# 32u4_Simple_Breakout.net
KiCad netlist of a schematic drawn in EAGLE
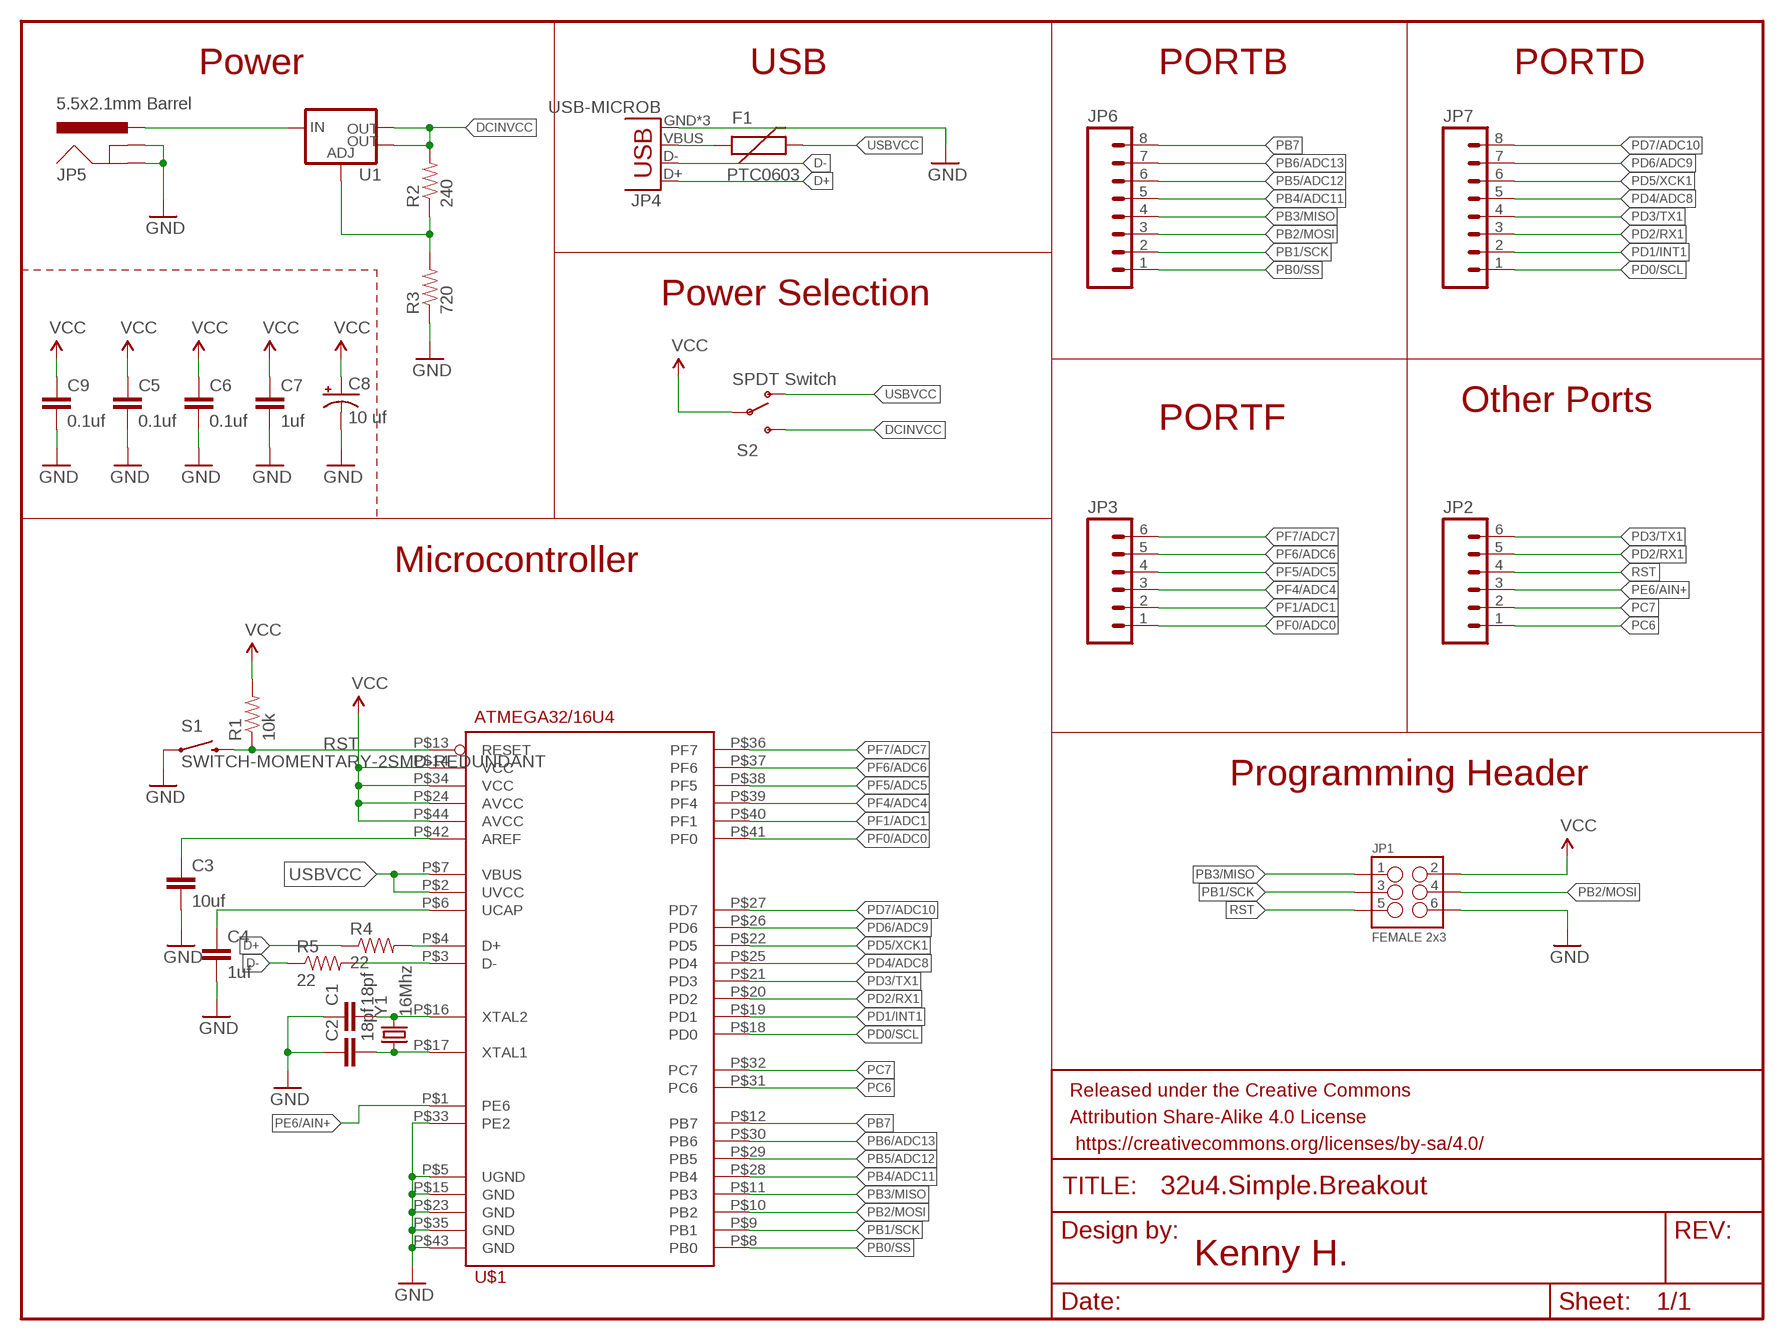
[diagram p0: schematic, sheet 1]

(export (version "E")
  (design (tool "Eeschema 10.0.6"))
  (components
    (comp (ref "C1")
      (value "18pf")
      (footprint "eagle-import:0603-CAP")
      (libsource (lib "eagle-import") (part "CAP0603-CAP"))
    )
    (comp (ref "C2")
      (value "18pf")
      (footprint "eagle-import:0603-CAP")
      (libsource (lib "eagle-import") (part "CAP0603-CAP"))
    )
    (comp (ref "C3")
      (value "10uf")
      (footprint "eagle-import:0603-CAP")
      (libsource (lib "eagle-import") (part "CAP0603-CAP"))
    )
    (comp (ref "C4")
      (value "1uf")
      (footprint "eagle-import:0603-CAP")
      (libsource (lib "eagle-import") (part "CAP0603-CAP"))
    )
    (comp (ref "C5")
      (value "0.1uf")
      (footprint "eagle-import:0603-CAP")
      (libsource (lib "eagle-import") (part "CAP0603-CAP"))
    )
    (comp (ref "C6")
      (value "0.1uf")
      (footprint "eagle-import:0603-CAP")
      (libsource (lib "eagle-import") (part "CAP0603-CAP"))
    )
    (comp (ref "C7")
      (value "1uf")
      (footprint "eagle-import:0603-CAP")
      (libsource (lib "eagle-import") (part "CAP0603-CAP"))
    )
    (comp (ref "C8")
      (value "10 uf")
      (footprint "eagle-import:CPOL-RADIAL-10UF-25V")
      (libsource (lib "eagle-import") (part "CAP_POLPTH2"))
    )
    (comp (ref "C9")
      (value "0.1uf")
      (footprint "eagle-import:0603-CAP")
      (libsource (lib "eagle-import") (part "CAP0603-CAP"))
    )
    (comp (ref "F1")
      (value "PTC0603")
      (footprint "eagle-import:0603")
      (libsource (lib "eagle-import") (part "PTC0603"))
    )
    (comp (ref "FRAME1")
      (value "FRAME-LETTER")
      (footprint "eagle-import:CREATIVE_COMMONS")
      (libsource (lib "eagle-import") (part "FRAME-LETTER"))
    )
    (comp (ref "JP1")
      (value "FEMALE 2x3")
      (footprint "eagle-import:2X3")
      (libsource (lib "eagle-import") (part "M03X2FEMALE"))
    )
    (comp (ref "JP2")
      (value "M06FEMALE_LOCK")
      (footprint "eagle-import:1X06_FEMALE_LOCK.010")
      (libsource (lib "eagle-import") (part "M06FEMALE_LOCK"))
    )
    (comp (ref "JP3")
      (value "M06FEMALE_LOCK")
      (footprint "eagle-import:1X06_FEMALE_LOCK.010")
      (libsource (lib "eagle-import") (part "M06FEMALE_LOCK"))
    )
    (comp (ref "JP4")
      (value "USB-MICROB")
      (footprint "eagle-import:USB-MICROB")
      (libsource (lib "eagle-import") (part "USB-MICROB"))
    )
    (comp (ref "JP5")
      (value "5.5x2.1mm Barrel")
      (footprint "eagle-import:POWER_JACK_SMD")
      (libsource (lib "eagle-import") (part "POWER_JACKSMD"))
    )
    (comp (ref "JP6")
      (value "M08FEMALE_LOCK")
      (footprint "eagle-import:1X08_FEMALE_LOCK")
      (libsource (lib "eagle-import") (part "M08FEMALE_LOCK"))
    )
    (comp (ref "JP7")
      (value "M08FEMALE_LOCK")
      (footprint "eagle-import:1X08_FEMALE_LOCK")
      (libsource (lib "eagle-import") (part "M08FEMALE_LOCK"))
    )
    (comp (ref "R1")
      (value "10k")
      (footprint "eagle-import:0603-RES")
      (libsource (lib "eagle-import") (part "RESISTOR0603-RES"))
    )
    (comp (ref "R2")
      (value "240")
      (footprint "eagle-import:0603-RES")
      (libsource (lib "eagle-import") (part "RESISTOR0603-RES"))
    )
    (comp (ref "R3")
      (value "720")
      (footprint "eagle-import:0603-RES")
      (libsource (lib "eagle-import") (part "RESISTOR0603-RES"))
    )
    (comp (ref "R4")
      (value "22")
      (footprint "eagle-import:0603-RES")
      (libsource (lib "eagle-import") (part "SparkFun-Resistors_RESISTOR0603-RES"))
    )
    (comp (ref "R5")
      (value "22")
      (footprint "eagle-import:0603-RES")
      (libsource (lib "eagle-import") (part "SparkFun-Resistors_RESISTOR0603-RES"))
    )
    (comp (ref "S1")
      (value "SWITCH-MOMENTARY-2SMD-REDUNDANT")
      (footprint "eagle-import:TACTILE-SWITCH-SMD")
      (libsource (lib "eagle-import") (part "SWITCH-MOMENTARY-2SMD-REDUNDANT"))
    )
    (comp (ref "S2")
      (value "SPDT Switch")
      (footprint "eagle-import:SWITCH-SPST-SMD-A")
      (libsource (lib "eagle-import") (part "SWITCH-SPDT-SMD-A"))
    )
    (comp (ref "U$1")
      (value "ATMEGA32/16U4")
      (footprint "eagle-import:TQFP_44_0.8MM")
      (libsource (lib "eagle-import") (part "ATMEGA32/16U4"))
    )
    (comp (ref "U1")
      (value "V_REG_LM1117SOT223")
      (footprint "eagle-import:SOT223")
      (libsource (lib "eagle-import") (part "V_REG_LM1117SOT223"))
    )
    (comp (ref "Y1")
      (value "16Mhz")
      (footprint "eagle-import:CRYSTAL-SMD-5X3")
      (libsource (lib "eagle-import") (part "CRYSTAL5X3"))
    )
  )
  (nets
    (net (code "1") (name "D+") (class "Default")
      (node (ref "JP4") (pin "D+") (pinfunction "D+_D+") (pintype "bidirectional"))
      (node (ref "R4") (pin "1") (pinfunction "1_1") (pintype "passive"))
    )
    (net (code "2") (name "D-") (class "Default")
      (node (ref "JP4") (pin "D-") (pinfunction "D-_D-") (pintype "bidirectional"))
      (node (ref "R5") (pin "1") (pinfunction "1_1") (pintype "passive"))
    )
    (net (code "3") (name "DCINVCC") (class "Default")
      (node (ref "R2") (pin "2") (pinfunction "2_2") (pintype "passive"))
      (node (ref "S2") (pin "3") (pinfunction "S_3") (pintype "passive"))
      (node (ref "U1") (pin "2") (pinfunction "OUT_2") (pintype "output"))
      (node (ref "U1") (pin "4") (pinfunction "OUT_4") (pintype "output"))
    )
    (net (code "4") (name "GND") (class "Default")
      (node (ref "C1") (pin "1") (pinfunction "1_1") (pintype "passive"))
      (node (ref "C2") (pin "1") (pinfunction "1_1") (pintype "passive"))
      (node (ref "C3") (pin "2") (pinfunction "2_2") (pintype "passive"))
      (node (ref "C4") (pin "2") (pinfunction "2_2") (pintype "passive"))
      (node (ref "C5") (pin "2") (pinfunction "2_2") (pintype "passive"))
      (node (ref "C6") (pin "2") (pinfunction "2_2") (pintype "passive"))
      (node (ref "C7") (pin "2") (pinfunction "2_2") (pintype "passive"))
      (node (ref "C8") (pin "2") (pinfunction "-_2") (pintype "passive"))
      (node (ref "C9") (pin "2") (pinfunction "2_2") (pintype "passive"))
      (node (ref "JP1") (pin "6") (pinfunction "6_6") (pintype "bidirectional"))
      (node (ref "JP4") (pin "GND") (pinfunction "GND_GND") (pintype "bidirectional"))
      (node (ref "JP4") (pin "MT1") (pinfunction "GND_MT1") (pintype "bidirectional"))
      (node (ref "JP4") (pin "MT2") (pinfunction "GND_MT2") (pintype "bidirectional"))
      (node (ref "JP5") (pin "GND") (pinfunction "GNDBREAK_GND") (pintype "bidirectional"))
      (node (ref "JP5") (pin "P$4") (pinfunction "GND_P$4") (pintype "bidirectional"))
      (node (ref "R3") (pin "1") (pinfunction "1_1") (pintype "passive"))
      (node (ref "S1") (pin "1") (pinfunction "1_1") (pintype "passive"))
      (node (ref "S1") (pin "2") (pinfunction "1_2") (pintype "passive"))
      (node (ref "U$1") (pin "P$15") (pinfunction "GND_P$15") (pintype "power_in"))
      (node (ref "U$1") (pin "P$23") (pinfunction "GND_P$23") (pintype "power_in"))
      (node (ref "U$1") (pin "P$33") (pinfunction "PE2_P$33") (pintype "bidirectional"))
      (node (ref "U$1") (pin "P$35") (pinfunction "GND_P$35") (pintype "power_in"))
      (node (ref "U$1") (pin "P$43") (pinfunction "GND_P$43") (pintype "power_in"))
      (node (ref "U$1") (pin "P$5") (pinfunction "UGND_P$5") (pintype "power_in"))
    )
    (net (code "5") (name "Net-(F1-Pad1)") (class "Default")
      (node (ref "F1") (pin "1") (pinfunction "1_1") (pintype "bidirectional"))
      (node (ref "JP4") (pin "VBUS") (pinfunction "VBUS_VBUS") (pintype "bidirectional"))
    )
    (net (code "6") (name "Net-(JP5-PWR)") (class "Default")
      (node (ref "JP5") (pin "VIN0") (pinfunction "PWR_VIN0") (pintype "bidirectional"))
      (node (ref "U1") (pin "3") (pinfunction "IN_3") (pintype "input"))
    )
    (net (code "7") (name "Net-(U$1-AREF)") (class "Default")
      (node (ref "C3") (pin "1") (pinfunction "1_1") (pintype "passive"))
      (node (ref "U$1") (pin "P$42") (pinfunction "AREF_P$42") (pintype "power_in"))
    )
    (net (code "8") (name "Net-(U$1-D+)") (class "Default")
      (node (ref "R4") (pin "2") (pinfunction "2_2") (pintype "passive"))
      (node (ref "U$1") (pin "P$4") (pinfunction "D+_P$4") (pintype "bidirectional"))
    )
    (net (code "9") (name "Net-(U$1-D-)") (class "Default")
      (node (ref "R5") (pin "2") (pinfunction "2_2") (pintype "passive"))
      (node (ref "U$1") (pin "P$3") (pinfunction "D-_P$3") (pintype "bidirectional"))
    )
    (net (code "10") (name "Net-(U$1-UCAP)") (class "Default")
      (node (ref "C4") (pin "1") (pinfunction "1_1") (pintype "passive"))
      (node (ref "U$1") (pin "P$6") (pinfunction "UCAP_P$6") (pintype "power_in"))
    )
    (net (code "11") (name "Net-(U$1-XTAL1)") (class "Default")
      (node (ref "C2") (pin "2") (pinfunction "2_2") (pintype "passive"))
      (node (ref "U$1") (pin "P$17") (pinfunction "XTAL1_P$17") (pintype "input"))
      (node (ref "Y1") (pin "1") (pinfunction "1_1") (pintype "passive"))
    )
    (net (code "12") (name "Net-(U$1-XTAL2)") (class "Default")
      (node (ref "C1") (pin "2") (pinfunction "2_2") (pintype "passive"))
      (node (ref "U$1") (pin "P$16") (pinfunction "XTAL2_P$16") (pintype "input"))
      (node (ref "Y1") (pin "3") (pinfunction "2_3") (pintype "passive"))
    )
    (net (code "13") (name "Net-(U1-ADJ)") (class "Default")
      (node (ref "R2") (pin "1") (pinfunction "1_1") (pintype "passive"))
      (node (ref "R3") (pin "2") (pinfunction "2_2") (pintype "passive"))
      (node (ref "U1") (pin "1") (pinfunction "ADJ_1") (pintype "input"))
    )
    (net (code "14") (name "PB0{slash}SS") (class "Default")
      (node (ref "JP6") (pin "1") (pinfunction "1_1") (pintype "passive"))
      (node (ref "U$1") (pin "P$8") (pinfunction "PB0_P$8") (pintype "bidirectional"))
    )
    (net (code "15") (name "PB1{slash}SCK") (class "Default")
      (node (ref "JP1") (pin "3") (pinfunction "3_3") (pintype "bidirectional"))
      (node (ref "JP6") (pin "2") (pinfunction "2_2") (pintype "passive"))
      (node (ref "U$1") (pin "P$9") (pinfunction "PB1_P$9") (pintype "bidirectional"))
    )
    (net (code "16") (name "PB2{slash}MOSI") (class "Default")
      (node (ref "JP1") (pin "4") (pinfunction "4_4") (pintype "bidirectional"))
      (node (ref "JP6") (pin "3") (pinfunction "3_3") (pintype "passive"))
      (node (ref "U$1") (pin "P$10") (pinfunction "PB2_P$10") (pintype "bidirectional"))
    )
    (net (code "17") (name "PB3{slash}MISO") (class "Default")
      (node (ref "JP1") (pin "1") (pinfunction "1_1") (pintype "bidirectional"))
      (node (ref "JP6") (pin "4") (pinfunction "4_4") (pintype "passive"))
      (node (ref "U$1") (pin "P$11") (pinfunction "PB3_P$11") (pintype "bidirectional"))
    )
    (net (code "18") (name "PB4{slash}ADC11") (class "Default")
      (node (ref "JP6") (pin "5") (pinfunction "5_5") (pintype "passive"))
      (node (ref "U$1") (pin "P$28") (pinfunction "PB4_P$28") (pintype "bidirectional"))
    )
    (net (code "19") (name "PB5{slash}ADC12") (class "Default")
      (node (ref "JP6") (pin "6") (pinfunction "6_6") (pintype "passive"))
      (node (ref "U$1") (pin "P$29") (pinfunction "PB5_P$29") (pintype "bidirectional"))
    )
    (net (code "20") (name "PB6{slash}ADC13") (class "Default")
      (node (ref "JP6") (pin "7") (pinfunction "7_7") (pintype "passive"))
      (node (ref "U$1") (pin "P$30") (pinfunction "PB6_P$30") (pintype "bidirectional"))
    )
    (net (code "21") (name "PB7") (class "Default")
      (node (ref "JP6") (pin "8") (pinfunction "8_8") (pintype "passive"))
      (node (ref "U$1") (pin "P$12") (pinfunction "PB7_P$12") (pintype "bidirectional"))
    )
    (net (code "22") (name "PC6") (class "Default")
      (node (ref "JP2") (pin "1") (pinfunction "1_1") (pintype "passive"))
      (node (ref "U$1") (pin "P$31") (pinfunction "PC6_P$31") (pintype "bidirectional"))
    )
    (net (code "23") (name "PC7") (class "Default")
      (node (ref "JP2") (pin "2") (pinfunction "2_2") (pintype "passive"))
      (node (ref "U$1") (pin "P$32") (pinfunction "PC7_P$32") (pintype "bidirectional"))
    )
    (net (code "24") (name "PD0{slash}SCL") (class "Default")
      (node (ref "JP7") (pin "1") (pinfunction "1_1") (pintype "passive"))
      (node (ref "U$1") (pin "P$18") (pinfunction "PD0_P$18") (pintype "bidirectional"))
    )
    (net (code "25") (name "PD1{slash}INT1") (class "Default")
      (node (ref "JP7") (pin "2") (pinfunction "2_2") (pintype "passive"))
      (node (ref "U$1") (pin "P$19") (pinfunction "PD1_P$19") (pintype "bidirectional"))
    )
    (net (code "26") (name "PD2{slash}RX1") (class "Default")
      (node (ref "JP2") (pin "5") (pinfunction "5_5") (pintype "passive"))
      (node (ref "JP7") (pin "3") (pinfunction "3_3") (pintype "passive"))
      (node (ref "U$1") (pin "P$20") (pinfunction "PD2_P$20") (pintype "bidirectional"))
    )
    (net (code "27") (name "PD3{slash}TX1") (class "Default")
      (node (ref "JP2") (pin "6") (pinfunction "6_6") (pintype "passive"))
      (node (ref "JP7") (pin "4") (pinfunction "4_4") (pintype "passive"))
      (node (ref "U$1") (pin "P$21") (pinfunction "PD3_P$21") (pintype "bidirectional"))
    )
    (net (code "28") (name "PD4{slash}ADC8") (class "Default")
      (node (ref "JP7") (pin "5") (pinfunction "5_5") (pintype "passive"))
      (node (ref "U$1") (pin "P$25") (pinfunction "PD4_P$25") (pintype "bidirectional"))
    )
    (net (code "29") (name "PD5{slash}XCK1") (class "Default")
      (node (ref "JP7") (pin "6") (pinfunction "6_6") (pintype "passive"))
      (node (ref "U$1") (pin "P$22") (pinfunction "PD5_P$22") (pintype "bidirectional"))
    )
    (net (code "30") (name "PD6{slash}ADC9") (class "Default")
      (node (ref "JP7") (pin "7") (pinfunction "7_7") (pintype "passive"))
      (node (ref "U$1") (pin "P$26") (pinfunction "PD6_P$26") (pintype "bidirectional"))
    )
    (net (code "31") (name "PD7{slash}ADC10") (class "Default")
      (node (ref "JP7") (pin "8") (pinfunction "8_8") (pintype "passive"))
      (node (ref "U$1") (pin "P$27") (pinfunction "PD7_P$27") (pintype "bidirectional"))
    )
    (net (code "32") (name "PE6{slash}AIN+") (class "Default")
      (node (ref "JP2") (pin "3") (pinfunction "3_3") (pintype "passive"))
      (node (ref "U$1") (pin "P$1") (pinfunction "PE6_P$1") (pintype "bidirectional"))
    )
    (net (code "33") (name "PF0{slash}ADC0") (class "Default")
      (node (ref "JP3") (pin "1") (pinfunction "1_1") (pintype "passive"))
      (node (ref "U$1") (pin "P$41") (pinfunction "PF0_P$41") (pintype "bidirectional"))
    )
    (net (code "34") (name "PF1{slash}ADC1") (class "Default")
      (node (ref "JP3") (pin "2") (pinfunction "2_2") (pintype "passive"))
      (node (ref "U$1") (pin "P$40") (pinfunction "PF1_P$40") (pintype "bidirectional"))
    )
    (net (code "35") (name "PF4{slash}ADC4") (class "Default")
      (node (ref "JP3") (pin "3") (pinfunction "3_3") (pintype "passive"))
      (node (ref "U$1") (pin "P$39") (pinfunction "PF4_P$39") (pintype "bidirectional"))
    )
    (net (code "36") (name "PF5{slash}ADC5") (class "Default")
      (node (ref "JP3") (pin "4") (pinfunction "4_4") (pintype "passive"))
      (node (ref "U$1") (pin "P$38") (pinfunction "PF5_P$38") (pintype "bidirectional"))
    )
    (net (code "37") (name "PF6{slash}ADC6") (class "Default")
      (node (ref "JP3") (pin "5") (pinfunction "5_5") (pintype "passive"))
      (node (ref "U$1") (pin "P$37") (pinfunction "PF6_P$37") (pintype "bidirectional"))
    )
    (net (code "38") (name "PF7{slash}ADC7") (class "Default")
      (node (ref "JP3") (pin "6") (pinfunction "6_6") (pintype "passive"))
      (node (ref "U$1") (pin "P$36") (pinfunction "PF7_P$36") (pintype "bidirectional"))
    )
    (net (code "39") (name "RST") (class "Default")
      (node (ref "JP1") (pin "5") (pinfunction "5_5") (pintype "bidirectional"))
      (node (ref "JP2") (pin "4") (pinfunction "4_4") (pintype "passive"))
      (node (ref "R1") (pin "1") (pinfunction "1_1") (pintype "passive"))
      (node (ref "S1") (pin "3") (pinfunction "2_3") (pintype "passive"))
      (node (ref "S1") (pin "4") (pinfunction "2_4") (pintype "passive"))
      (node (ref "U$1") (pin "P$13") (pinfunction "RESET_P$13") (pintype "input"))
    )
    (net (code "40") (name "USBVCC") (class "Default")
      (node (ref "F1") (pin "2") (pinfunction "2_2") (pintype "bidirectional"))
      (node (ref "S2") (pin "1") (pinfunction "O_1") (pintype "passive"))
      (node (ref "U$1") (pin "P$2") (pinfunction "UVCC_P$2") (pintype "power_in"))
      (node (ref "U$1") (pin "P$7") (pinfunction "VBUS_P$7") (pintype "power_in"))
    )
    (net (code "41") (name "VCC") (class "Default")
      (node (ref "C5") (pin "1") (pinfunction "1_1") (pintype "passive"))
      (node (ref "C6") (pin "1") (pinfunction "1_1") (pintype "passive"))
      (node (ref "C7") (pin "1") (pinfunction "1_1") (pintype "passive"))
      (node (ref "C8") (pin "1") (pinfunction "+_1") (pintype "passive"))
      (node (ref "C9") (pin "1") (pinfunction "1_1") (pintype "passive"))
      (node (ref "JP1") (pin "2") (pinfunction "2_2") (pintype "bidirectional"))
      (node (ref "R1") (pin "2") (pinfunction "2_2") (pintype "passive"))
      (node (ref "S2") (pin "2") (pinfunction "P_2") (pintype "passive"))
      (node (ref "U$1") (pin "P$14") (pinfunction "VCC_P$14") (pintype "power_in"))
      (node (ref "U$1") (pin "P$24") (pinfunction "AVCC_P$24") (pintype "power_in"))
      (node (ref "U$1") (pin "P$34") (pinfunction "VCC_P$34") (pintype "power_in"))
      (node (ref "U$1") (pin "P$44") (pinfunction "AVCC_P$44") (pintype "power_in"))
    )
  )
)
